# Pump_Fan_Control.net
KiCad netlist of a schematic drawn in Altium Designer
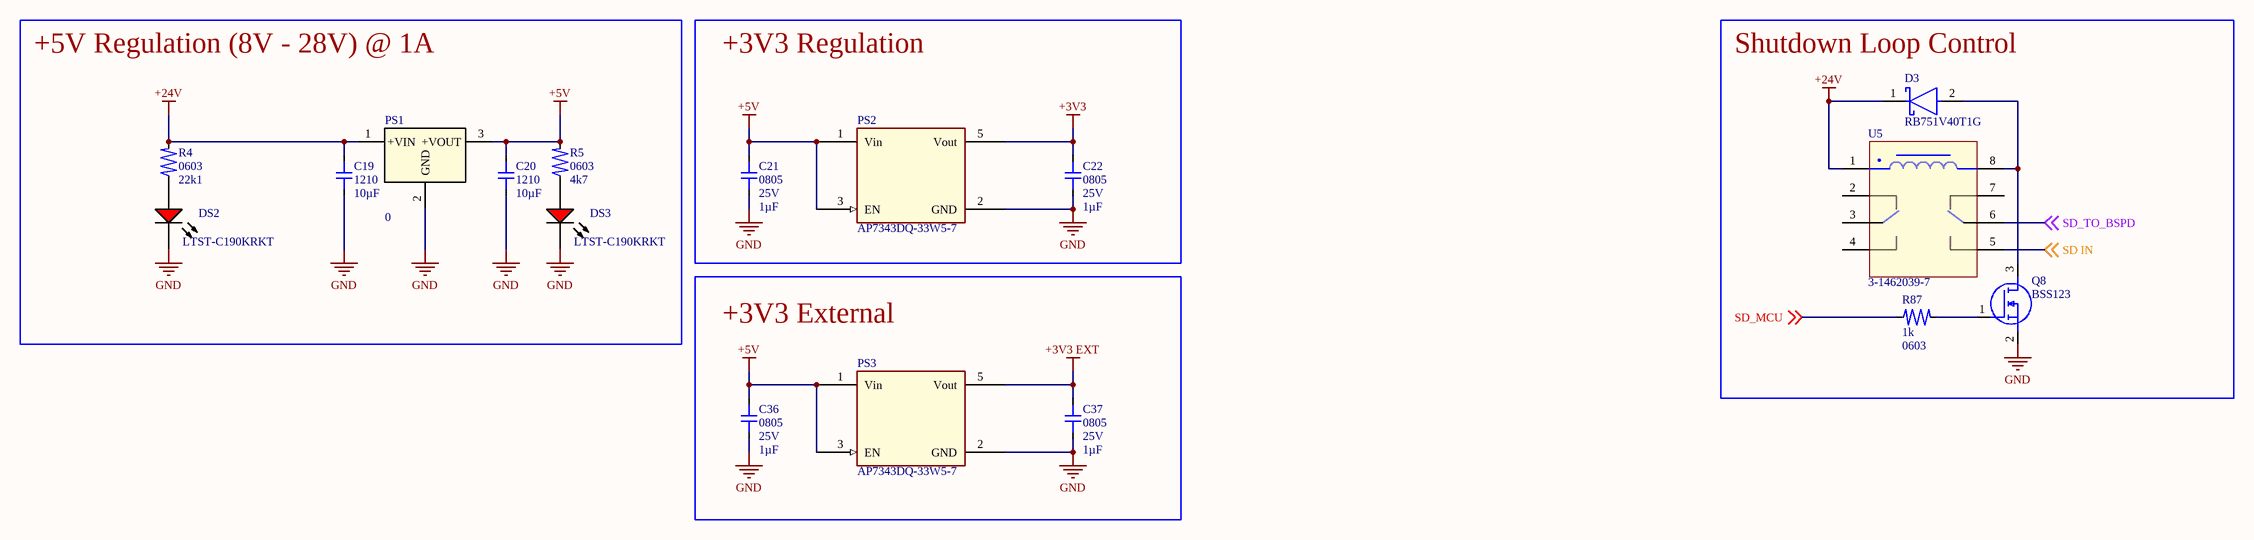
[diagram p0: Pump Fan Control.SchDoc]

(export (version "E")
  (design (tool "Eeschema 10.0.6"))
  (components
    (comp (ref "C19")
      (value "10µF")
      (footprint "1210")
      (description "Capacitor 1210")
      (fields (field (name "Comment") "Capacitor 10uF 1210 50V"))
      (libsource (lib "Zips Racing Electric") (part "CAP-0603"))
    )
    (comp (ref "C20")
      (value "10µF")
      (footprint "1210")
      (description "Capacitor 1210")
      (fields (field (name "Comment") "Capacitor 10uF 1210 50V"))
      (libsource (lib "Zips Racing Electric") (part "CAP-0603"))
    )
    (comp (ref "C21")
      (value "1µF")
      (footprint "0805")
      (description "Capacitor, 0805")
      (fields (field (name "VOLTAGE") "25V") (field (name "Comment") "Capacitor 1uF 0805 25V"))
      (libsource (lib "Zips Racing Electric") (part "CAP-0603"))
    )
    (comp (ref "C22")
      (value "1µF")
      (footprint "0805")
      (description "Capacitor, 0805")
      (fields (field (name "VOLTAGE") "25V") (field (name "Comment") "Capacitor 1uF 0805 25V"))
      (libsource (lib "Zips Racing Electric") (part "CAP-0603"))
    )
    (comp (ref "C36")
      (value "1µF")
      (footprint "0805")
      (description "Capacitor, 0805")
      (fields (field (name "VOLTAGE") "25V") (field (name "Comment") "Capacitor 1uF 0805 25V"))
      (libsource (lib "Zips Racing Electric") (part "CAP-0603"))
    )
    (comp (ref "C37")
      (value "1µF")
      (footprint "0805")
      (description "Capacitor, 0805")
      (fields (field (name "VOLTAGE") "25V") (field (name "Comment") "Capacitor 1uF 0805 25V"))
      (libsource (lib "Zips Racing Electric") (part "CAP-0603"))
    )
    (comp (ref "D3")
      (value "RB751V40T1G")
      (footprint "FP-477-02-MFG")
      (description "Rectifier Diode, Schottky, 1 Phase, 1 Element, 0.03A, 40V V(RRM), Silicon")
      (libsource (lib "Zips Racing Electric") (part "1d6ec82d83fb6aee721767c19dac4b9"))
    )
    (comp (ref "DS2")
      (value "LTST-C190KRKT")
      (footprint "LTST-C191KRKT_V")
      (description "LED Uni-Color Red, 62.5 mW, 25 mA, -30 to 85 degC, 2-Pin SMD, RoHS, Tape and Reel")
      (fields (field (name "POWER") "75mW") (field (name "MANUFACTURER") "Lite-On"))
      (libsource (lib "Zips Racing Electric") (part "LED-RED-AK-2"))
    )
    (comp (ref "DS3")
      (value "LTST-C190KRKT")
      (footprint "LTST-C191KRKT_V")
      (description "LED Uni-Color Red, 62.5 mW, 25 mA, -30 to 85 degC, 2-Pin SMD, RoHS, Tape and Reel")
      (fields (field (name "POWER") "75mW") (field (name "MANUFACTURER") "Lite-On"))
      (libsource (lib "Zips Racing Electric") (part "LED-RED-AK-2"))
    )
    (comp (ref "PS1")
      (value "0")
      (footprint "CONV_R-78E5.0-1.0")
      (description "Linear Regulator Replacement DC DC Converter 1 Output 5V - - 1A 8V - 28V Input")
      (fields
        (field (name "MF") "Recom Power")
        (field (name "MP") "R-78E5.0-1.0")
        (field (name "SOURCE") "Zips_Racing_Electric.SchLib")
      )
      (libsource (lib "Zips Racing Electric") (part "R-78E5.0-1.0"))
    )
    (comp (ref "PS2")
      (value "AP7343DQ-33W5-7")
      (footprint "SOT95P285X140-5N")
      (description "Fixed Positive LDO Regulator")
      (libsource (lib "Zips Racing Electric") (part "AP7343DQ-33W5-7-Symbol-1"))
    )
    (comp (ref "PS3")
      (value "AP7343DQ-33W5-7")
      (footprint "SOT95P285X140-5N")
      (description "Fixed Positive LDO Regulator")
      (libsource (lib "Zips Racing Electric") (part "AP7343DQ-33W5-7-Symbol-1"))
    )
    (comp (ref "Q8")
      (value "BSS123")
      (footprint "SOT96P237X111-3N")
      (description "MOSFET N-CH 100V 170MA SOT23-3")
      (fields
        (field (name "MOUSER PART NUMBER") "512-BSS123")
        (field (name "SOURCE") "Zips_Racing_Electric.SchLib")
      )
      (libsource (lib "Zips Racing Electric") (part "BSS123"))
    )
    (comp (ref "R4")
      (value "22k1")
      (footprint "0603")
      (description "Resistor, 0603, 1%, 1/10W")
      (fields (field (name "TOLERANCE") "1%") (field (name "POWER") "100mW"))
      (libsource (lib "Zips Racing Electric") (part "RES-0603"))
    )
    (comp (ref "R5")
      (value "4k7")
      (footprint "0603")
      (description "Resistor, 0603, 1%, 1/10W")
      (fields (field (name "TOLERANCE") "1%") (field (name "POWER") "100mW"))
      (libsource (lib "Zips Racing Electric") (part "RES-0603"))
    )
    (comp (ref "R87")
      (value "1k")
      (footprint "0603")
      (description "Resistor, 0603, 1k")
      (fields (field (name "POWER") "100mW") (field (name "TOLERANCE") "1%"))
      (libsource (lib "Zips Racing Electric") (part "RES-0603"))
    )
    (comp (ref "U5")
      (value "3-1462039-7")
      (footprint "3-1462039-7-Footprint-1")
      (libsource (lib "Zips Racing Electric") (part "3-1462039-7-Symbol-1"))
    )
  )
  (nets
    (net (code "1") (name "+3V3") (class "Default")
      (node (ref "C22") (pin "2") (pinfunction "2_2") (pintype "passive"))
      (node (ref "PS2") (pin "5") (pinfunction "Vout_5") (pintype "power_in"))
    )
    (net (code "2") (name "+3V3 EXT") (class "Default")
      (node (ref "C37") (pin "2") (pinfunction "2_2") (pintype "passive"))
      (node (ref "PS3") (pin "5") (pinfunction "Vout_5") (pintype "power_in"))
    )
    (net (code "3") (name "+5V") (class "Default")
      (node (ref "C20") (pin "2") (pinfunction "2_2") (pintype "passive"))
      (node (ref "C21") (pin "2") (pinfunction "2_2") (pintype "passive"))
      (node (ref "C36") (pin "2") (pinfunction "2_2") (pintype "passive"))
      (node (ref "PS1") (pin "3") (pinfunction "+VOUT_3") (pintype "passive"))
      (node (ref "PS2") (pin "1") (pinfunction "Vin_1") (pintype "power_in"))
      (node (ref "PS2") (pin "3") (pinfunction "EN_3") (pintype "input"))
      (node (ref "PS3") (pin "1") (pinfunction "Vin_1") (pintype "power_in"))
      (node (ref "PS3") (pin "3") (pinfunction "EN_3") (pintype "input"))
      (node (ref "R5") (pin "2") (pinfunction "2_2") (pintype "passive"))
    )
    (net (code "4") (name "+24V") (class "Default")
      (node (ref "C19") (pin "2") (pinfunction "2_2") (pintype "passive"))
      (node (ref "D3") (pin "1") (pinfunction "C_1") (pintype "passive"))
      (node (ref "PS1") (pin "1") (pinfunction "+VIN_1") (pintype "passive"))
      (node (ref "R4") (pin "2") (pinfunction "2_2") (pintype "passive"))
      (node (ref "U5") (pin "1") (pinfunction "1_1") (pintype "passive"))
    )
    (net (code "5") (name "GND") (class "Default")
      (node (ref "C19") (pin "1") (pinfunction "1_1") (pintype "passive"))
      (node (ref "C20") (pin "1") (pinfunction "1_1") (pintype "passive"))
      (node (ref "C21") (pin "1") (pinfunction "1_1") (pintype "passive"))
      (node (ref "C22") (pin "1") (pinfunction "1_1") (pintype "passive"))
      (node (ref "C36") (pin "1") (pinfunction "1_1") (pintype "passive"))
      (node (ref "C37") (pin "1") (pinfunction "1_1") (pintype "passive"))
      (node (ref "DS2") (pin "2") (pinfunction "K_2") (pintype "passive"))
      (node (ref "DS3") (pin "2") (pinfunction "K_2") (pintype "passive"))
      (node (ref "PS1") (pin "2") (pinfunction "GND_2") (pintype "power_in"))
      (node (ref "PS2") (pin "2") (pinfunction "GND_2") (pintype "power_in"))
      (node (ref "PS3") (pin "2") (pinfunction "GND_2") (pintype "power_in"))
      (node (ref "Q8") (pin "2") (pinfunction "S_2") (pintype "passive"))
    )
    (net (code "6") (name "Net-(D3-A)") (class "Default")
      (node (ref "D3") (pin "2") (pinfunction "A_2") (pintype "passive"))
      (node (ref "Q8") (pin "3") (pinfunction "D_3") (pintype "passive"))
      (node (ref "U5") (pin "8") (pinfunction "8_8") (pintype "passive"))
    )
    (net (code "7") (name "Net-(DS2-A)") (class "Default")
      (node (ref "DS2") (pin "1") (pinfunction "A_1") (pintype "passive"))
      (node (ref "R4") (pin "1") (pinfunction "1_1") (pintype "passive"))
    )
    (net (code "8") (name "Net-(DS3-A)") (class "Default")
      (node (ref "DS3") (pin "1") (pinfunction "A_1") (pintype "passive"))
      (node (ref "R5") (pin "1") (pinfunction "1_1") (pintype "passive"))
    )
    (net (code "9") (name "Net-(Q8-G)") (class "Default")
      (node (ref "Q8") (pin "1") (pinfunction "G_1") (pintype "passive"))
      (node (ref "R87") (pin "2") (pinfunction "2_2") (pintype "passive"))
    )
    (net (code "10") (name "SD IN") (class "Default")
      (node (ref "U5") (pin "5") (pinfunction "5_5") (pintype "passive"))
    )
    (net (code "11") (name "SD_MCU") (class "Default")
      (node (ref "R87") (pin "1") (pinfunction "1_1") (pintype "passive"))
    )
    (net (code "12") (name "SD_TO_BSPD") (class "Default")
      (node (ref "U5") (pin "6") (pinfunction "6_6") (pintype "passive"))
    )
    (net (code "13") (name "unconnected-(PS2-NC-Pad4)") (class "Default")
      (node (ref "PS2") (pin "4") (pinfunction "NC_4") (pintype "passive"))
    )
    (net (code "14") (name "unconnected-(PS3-NC-Pad4)") (class "Default")
      (node (ref "PS3") (pin "4") (pinfunction "NC_4") (pintype "passive"))
    )
    (net (code "15") (name "unconnected-(U5-Pad2)") (class "Default")
      (node (ref "U5") (pin "2") (pinfunction "2_2") (pintype "passive"))
    )
    (net (code "16") (name "unconnected-(U5-Pad3)") (class "Default")
      (node (ref "U5") (pin "3") (pinfunction "3_3") (pintype "passive"))
    )
    (net (code "17") (name "unconnected-(U5-Pad4)") (class "Default")
      (node (ref "U5") (pin "4") (pinfunction "4_4") (pintype "passive"))
    )
    (net (code "18") (name "unconnected-(U5-Pad7)") (class "Default")
      (node (ref "U5") (pin "7") (pinfunction "7_7") (pintype "passive"))
    )
  )
)
